# Stuff.net
KiCad netlist of a schematic drawn in Altium Designer
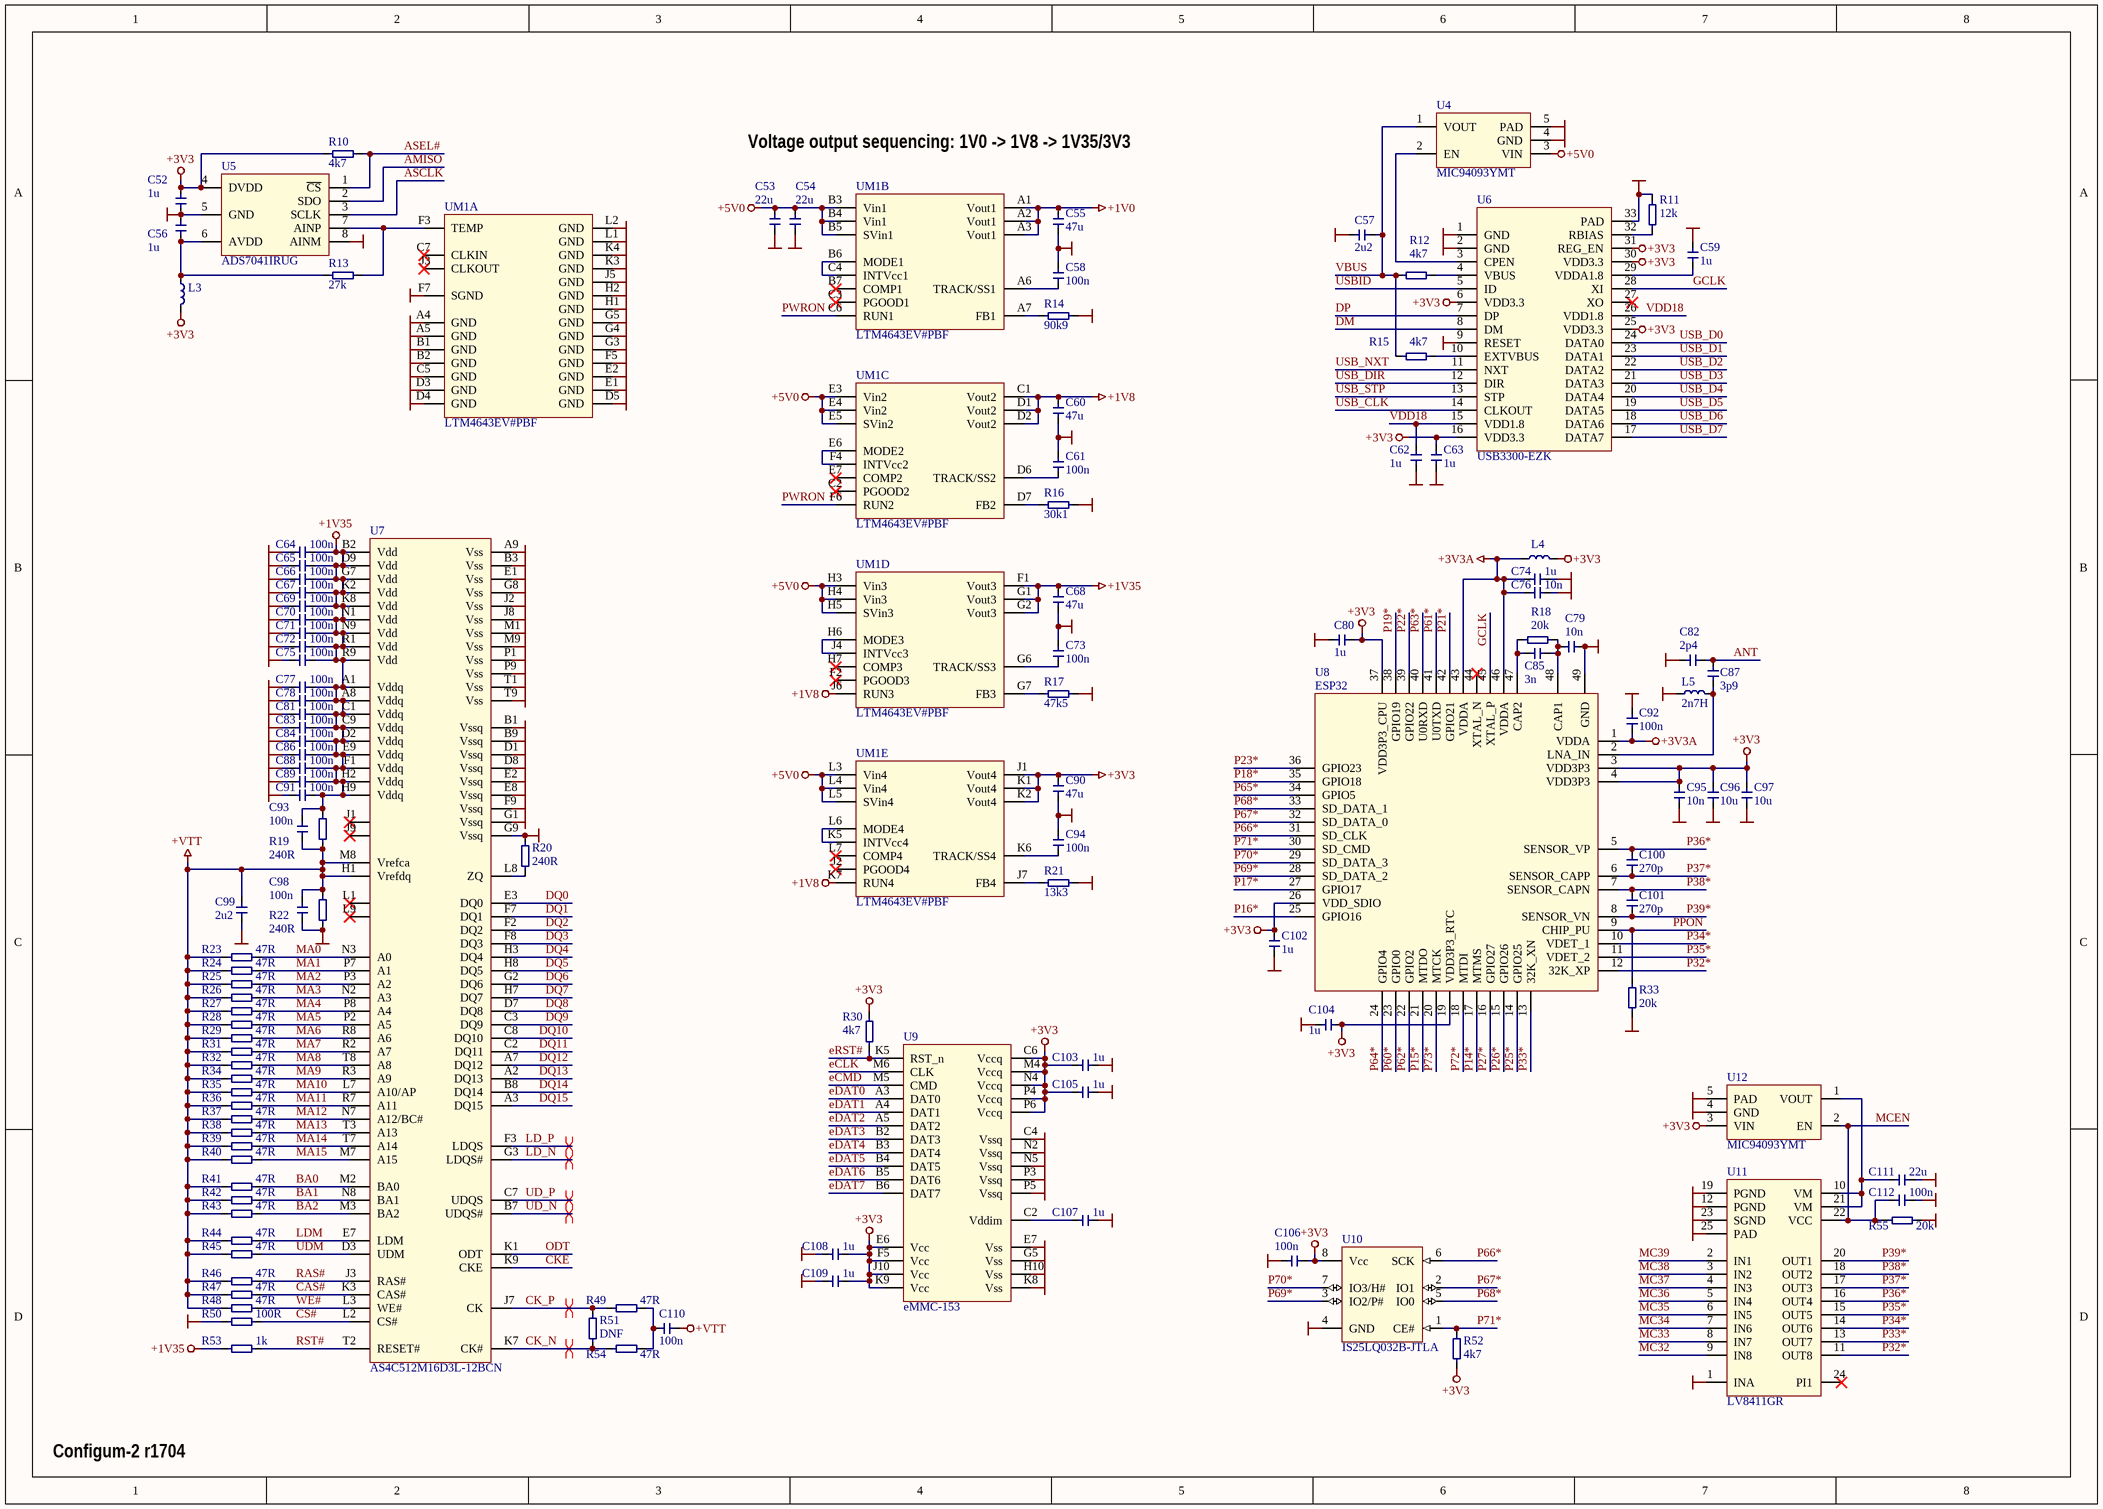
[diagram p0: Stuff.SchDoc]

(export (version "E")
  (design (tool "Eeschema 10.0.6"))
  (components
    (comp (ref "C52")
      (value "1u")
      (footprint "_0201")
      (description "Capacitor")
      (libsource (lib "Discretes") (part "Capacitor"))
    )
    (comp (ref "C53")
      (value "22u")
      (footprint "_0805_CAP")
      (description "Capacitor")
      (libsource (lib "Discretes") (part "Capacitor"))
    )
    (comp (ref "C54")
      (value "22u")
      (footprint "_0805_CAP")
      (description "Capacitor")
      (libsource (lib "Discretes") (part "Capacitor"))
    )
    (comp (ref "C55")
      (value "47u")
      (footprint "_0805_CAP")
      (description "Capacitor")
      (libsource (lib "Discretes") (part "Capacitor"))
    )
    (comp (ref "C56")
      (value "1u")
      (footprint "_0201")
      (description "Capacitor")
      (libsource (lib "Discretes") (part "Capacitor"))
    )
    (comp (ref "C57")
      (value "2u2")
      (footprint "_0201")
      (description "Capacitor")
      (libsource (lib "Discretes") (part "Capacitor"))
    )
    (comp (ref "C58")
      (value "100n")
      (footprint "_0201")
      (description "Capacitor")
      (libsource (lib "Discretes") (part "Capacitor"))
    )
    (comp (ref "C59")
      (value "1u")
      (footprint "_0201")
      (description "Capacitor")
      (libsource (lib "Discretes") (part "Capacitor"))
    )
    (comp (ref "C60")
      (value "47u")
      (footprint "_0805_CAP")
      (description "Capacitor")
      (libsource (lib "Discretes") (part "Capacitor"))
    )
    (comp (ref "C61")
      (value "100n")
      (footprint "_0201")
      (description "Capacitor")
      (libsource (lib "Discretes") (part "Capacitor"))
    )
    (comp (ref "C62")
      (value "1u")
      (footprint "_0201")
      (description "Capacitor")
      (libsource (lib "Discretes") (part "Capacitor"))
    )
    (comp (ref "C63")
      (value "1u")
      (footprint "_0201")
      (description "Capacitor")
      (libsource (lib "Discretes") (part "Capacitor"))
    )
    (comp (ref "C64")
      (value "100n")
      (footprint "_0201")
      (description "Capacitor")
      (libsource (lib "Discretes") (part "Capacitor"))
    )
    (comp (ref "C65")
      (value "100n")
      (footprint "_0201")
      (description "Capacitor")
      (libsource (lib "Discretes") (part "Capacitor"))
    )
    (comp (ref "C66")
      (value "100n")
      (footprint "_0201")
      (description "Capacitor")
      (libsource (lib "Discretes") (part "Capacitor"))
    )
    (comp (ref "C67")
      (value "100n")
      (footprint "_0201")
      (description "Capacitor")
      (libsource (lib "Discretes") (part "Capacitor"))
    )
    (comp (ref "C68")
      (value "47u")
      (footprint "_0805_CAP")
      (description "Capacitor")
      (libsource (lib "Discretes") (part "Capacitor"))
    )
    (comp (ref "C69")
      (value "100n")
      (footprint "_0201")
      (description "Capacitor")
      (libsource (lib "Discretes") (part "Capacitor"))
    )
    (comp (ref "C70")
      (value "100n")
      (footprint "_0201")
      (description "Capacitor")
      (libsource (lib "Discretes") (part "Capacitor"))
    )
    (comp (ref "C71")
      (value "100n")
      (footprint "_0201")
      (description "Capacitor")
      (libsource (lib "Discretes") (part "Capacitor"))
    )
    (comp (ref "C72")
      (value "100n")
      (footprint "_0201")
      (description "Capacitor")
      (libsource (lib "Discretes") (part "Capacitor"))
    )
    (comp (ref "C73")
      (value "100n")
      (footprint "_0201")
      (description "Capacitor")
      (libsource (lib "Discretes") (part "Capacitor"))
    )
    (comp (ref "C74")
      (value "1u")
      (footprint "_0201")
      (description "Capacitor")
      (libsource (lib "Discretes") (part "Capacitor"))
    )
    (comp (ref "C75")
      (value "100n")
      (footprint "_0201")
      (description "Capacitor")
      (libsource (lib "Discretes") (part "Capacitor"))
    )
    (comp (ref "C76")
      (value "10n")
      (footprint "_0201")
      (description "Capacitor")
      (libsource (lib "Discretes") (part "Capacitor"))
    )
    (comp (ref "C77")
      (value "100n")
      (footprint "_0201")
      (description "Capacitor")
      (libsource (lib "Discretes") (part "Capacitor"))
    )
    (comp (ref "C78")
      (value "100n")
      (footprint "_0201")
      (description "Capacitor")
      (libsource (lib "Discretes") (part "Capacitor"))
    )
    (comp (ref "C79")
      (value "10n")
      (footprint "_0201")
      (description "Capacitor")
      (libsource (lib "Discretes") (part "Capacitor"))
    )
    (comp (ref "C80")
      (value "1u")
      (footprint "_0201")
      (description "Capacitor")
      (libsource (lib "Discretes") (part "Capacitor"))
    )
    (comp (ref "C81")
      (value "100n")
      (footprint "_0201")
      (description "Capacitor")
      (libsource (lib "Discretes") (part "Capacitor"))
    )
    (comp (ref "C82")
      (value "2p4")
      (footprint "_0201")
      (description "Capacitor")
      (libsource (lib "Discretes") (part "Capacitor"))
    )
    (comp (ref "C83")
      (value "100n")
      (footprint "_0201")
      (description "Capacitor")
      (libsource (lib "Discretes") (part "Capacitor"))
    )
    (comp (ref "C84")
      (value "100n")
      (footprint "_0201")
      (description "Capacitor")
      (libsource (lib "Discretes") (part "Capacitor"))
    )
    (comp (ref "C85")
      (value "3n")
      (footprint "_0201")
      (description "Capacitor")
      (libsource (lib "Discretes") (part "Capacitor"))
    )
    (comp (ref "C86")
      (value "100n")
      (footprint "_0201")
      (description "Capacitor")
      (libsource (lib "Discretes") (part "Capacitor"))
    )
    (comp (ref "C87")
      (value "3p9")
      (footprint "_0201")
      (description "Capacitor")
      (libsource (lib "Discretes") (part "Capacitor"))
    )
    (comp (ref "C88")
      (value "100n")
      (footprint "_0201")
      (description "Capacitor")
      (libsource (lib "Discretes") (part "Capacitor"))
    )
    (comp (ref "C89")
      (value "100n")
      (footprint "_0201")
      (description "Capacitor")
      (libsource (lib "Discretes") (part "Capacitor"))
    )
    (comp (ref "C90")
      (value "47u")
      (footprint "_0805_CAP")
      (description "Capacitor")
      (libsource (lib "Discretes") (part "Capacitor"))
    )
    (comp (ref "C91")
      (value "100n")
      (footprint "_0201")
      (description "Capacitor")
      (libsource (lib "Discretes") (part "Capacitor"))
    )
    (comp (ref "C92")
      (value "100n")
      (footprint "_0201")
      (description "Capacitor")
      (libsource (lib "Discretes") (part "Capacitor"))
    )
    (comp (ref "C93")
      (value "100n")
      (footprint "_0201")
      (description "Capacitor")
      (libsource (lib "Discretes") (part "Capacitor"))
    )
    (comp (ref "C94")
      (value "100n")
      (footprint "_0201")
      (description "Capacitor")
      (libsource (lib "Discretes") (part "Capacitor"))
    )
    (comp (ref "C95")
      (value "10n")
      (footprint "_0201")
      (description "Capacitor")
      (libsource (lib "Discretes") (part "Capacitor"))
    )
    (comp (ref "C96")
      (value "10u")
      (footprint "_0603")
      (description "Capacitor")
      (libsource (lib "Discretes") (part "Capacitor"))
    )
    (comp (ref "C97")
      (value "10u")
      (footprint "_0603")
      (description "Capacitor")
      (libsource (lib "Discretes") (part "Capacitor"))
    )
    (comp (ref "C98")
      (value "100n")
      (footprint "_0201")
      (description "Capacitor")
      (libsource (lib "Discretes") (part "Capacitor"))
    )
    (comp (ref "C99")
      (value "2u2")
      (footprint "_0201")
      (description "Capacitor")
      (libsource (lib "Discretes") (part "Capacitor"))
    )
    (comp (ref "C100")
      (value "270p")
      (footprint "_0201")
      (description "Capacitor")
      (libsource (lib "Discretes") (part "Capacitor"))
    )
    (comp (ref "C101")
      (value "270p")
      (footprint "_0201")
      (description "Capacitor")
      (libsource (lib "Discretes") (part "Capacitor"))
    )
    (comp (ref "C102")
      (value "1u")
      (footprint "_0201")
      (description "Capacitor")
      (libsource (lib "Discretes") (part "Capacitor"))
    )
    (comp (ref "C103")
      (value "1u")
      (footprint "_0201")
      (description "Capacitor")
      (libsource (lib "Discretes") (part "Capacitor"))
    )
    (comp (ref "C104")
      (value "1u")
      (footprint "_0201")
      (description "Capacitor")
      (libsource (lib "Discretes") (part "Capacitor"))
    )
    (comp (ref "C105")
      (value "1u")
      (footprint "_0201")
      (description "Capacitor")
      (libsource (lib "Discretes") (part "Capacitor"))
    )
    (comp (ref "C106")
      (value "100n")
      (footprint "_0201")
      (description "Capacitor")
      (libsource (lib "Discretes") (part "Capacitor"))
    )
    (comp (ref "C107")
      (value "1u")
      (footprint "_0201")
      (description "Capacitor")
      (libsource (lib "Discretes") (part "Capacitor"))
    )
    (comp (ref "C108")
      (value "1u")
      (footprint "_0201")
      (description "Capacitor")
      (libsource (lib "Discretes") (part "Capacitor"))
    )
    (comp (ref "C109")
      (value "1u")
      (footprint "_0201")
      (description "Capacitor")
      (libsource (lib "Discretes") (part "Capacitor"))
    )
    (comp (ref "C110")
      (value "100n")
      (footprint "_0201")
      (description "Capacitor")
      (libsource (lib "Discretes") (part "Capacitor"))
    )
    (comp (ref "C111")
      (value "22u")
      (footprint "_0805_CAP")
      (description "Capacitor")
      (libsource (lib "Discretes") (part "Capacitor"))
    )
    (comp (ref "C112")
      (value "100n")
      (footprint "_0201")
      (description "Capacitor")
      (libsource (lib "Discretes") (part "Capacitor"))
    )
    (comp (ref "L3")
      (value "60R/100MHz")
      (footprint "_0201")
      (description "Inductor")
      (libsource (lib "Discretes") (part "Inductor"))
    )
    (comp (ref "L4")
      (value "60R/100MHz")
      (footprint "_0201")
      (description "Inductor")
      (libsource (lib "") (part "Inductor_1"))
    )
    (comp (ref "L5")
      (value "2n7H")
      (footprint "_0201")
      (description "Inductor")
      (libsource (lib "") (part "Inductor_1"))
    )
    (comp (ref "R10")
      (value "4k7")
      (footprint "_0201")
      (description "Resistor")
      (libsource (lib "") (part "Resistor_2"))
    )
    (comp (ref "R11")
      (value "12k")
      (footprint "_0201")
      (description "Resistor")
      (libsource (lib "") (part "Resistor_3"))
    )
    (comp (ref "R12")
      (value "4k7")
      (footprint "_0201")
      (description "Resistor")
      (libsource (lib "Discretes") (part "Resistor"))
    )
    (comp (ref "R13")
      (value "27k")
      (footprint "_0201")
      (description "Resistor")
      (libsource (lib "") (part "Resistor_2"))
    )
    (comp (ref "R14")
      (value "90k9")
      (footprint "_0201")
      (description "Resistor")
      (libsource (lib "Discretes") (part "Resistor"))
    )
    (comp (ref "R15")
      (value "4k7")
      (footprint "_0201")
      (description "Resistor")
      (libsource (lib "Discretes") (part "Resistor"))
    )
    (comp (ref "R16")
      (value "30k1")
      (footprint "_0201")
      (description "Resistor")
      (libsource (lib "Discretes") (part "Resistor"))
    )
    (comp (ref "R17")
      (value "47k5")
      (footprint "_0201")
      (description "Resistor")
      (libsource (lib "Discretes") (part "Resistor"))
    )
    (comp (ref "R18")
      (value "20k")
      (footprint "_0201")
      (description "Resistor")
      (libsource (lib "Discretes") (part "Resistor"))
    )
    (comp (ref "R19")
      (value "240R")
      (footprint "_0201")
      (description "Resistor")
      (libsource (lib "") (part "Resistor_1"))
    )
    (comp (ref "R20")
      (value "240R")
      (footprint "_0201")
      (description "Resistor")
      (libsource (lib "") (part "Resistor_1"))
    )
    (comp (ref "R21")
      (value "13k3")
      (footprint "_0201")
      (description "Resistor")
      (libsource (lib "Discretes") (part "Resistor"))
    )
    (comp (ref "R22")
      (value "240R")
      (footprint "_0201")
      (description "Resistor")
      (libsource (lib "") (part "Resistor_1"))
    )
    (comp (ref "R23")
      (value "47R")
      (footprint "_0201")
      (description "Resistor")
      (libsource (lib "") (part "Resistor_1"))
    )
    (comp (ref "R24")
      (value "47R")
      (footprint "_0201")
      (description "Resistor")
      (libsource (lib "") (part "Resistor_1"))
    )
    (comp (ref "R25")
      (value "47R")
      (footprint "_0201")
      (description "Resistor")
      (libsource (lib "") (part "Resistor_1"))
    )
    (comp (ref "R26")
      (value "47R")
      (footprint "_0201")
      (description "Resistor")
      (libsource (lib "") (part "Resistor_1"))
    )
    (comp (ref "R27")
      (value "47R")
      (footprint "_0201")
      (description "Resistor")
      (libsource (lib "") (part "Resistor_1"))
    )
    (comp (ref "R28")
      (value "47R")
      (footprint "_0201")
      (description "Resistor")
      (libsource (lib "") (part "Resistor_1"))
    )
    (comp (ref "R29")
      (value "47R")
      (footprint "_0201")
      (description "Resistor")
      (libsource (lib "") (part "Resistor_1"))
    )
    (comp (ref "R30")
      (value "4k7")
      (footprint "_0201")
      (description "Resistor")
      (libsource (lib "") (part "Resistor_1"))
    )
    (comp (ref "R31")
      (value "47R")
      (footprint "_0201")
      (description "Resistor")
      (libsource (lib "") (part "Resistor_1"))
    )
    (comp (ref "R32")
      (value "47R")
      (footprint "_0201")
      (description "Resistor")
      (libsource (lib "") (part "Resistor_1"))
    )
    (comp (ref "R33")
      (value "20k")
      (footprint "_0201")
      (description "Resistor")
      (libsource (lib "") (part "Resistor_1"))
    )
    (comp (ref "R34")
      (value "47R")
      (footprint "_0201")
      (description "Resistor")
      (libsource (lib "") (part "Resistor_1"))
    )
    (comp (ref "R35")
      (value "47R")
      (footprint "_0201")
      (description "Resistor")
      (libsource (lib "") (part "Resistor_1"))
    )
    (comp (ref "R36")
      (value "47R")
      (footprint "_0201")
      (description "Resistor")
      (libsource (lib "") (part "Resistor_1"))
    )
    (comp (ref "R37")
      (value "47R")
      (footprint "_0201")
      (description "Resistor")
      (libsource (lib "") (part "Resistor_1"))
    )
    (comp (ref "R38")
      (value "47R")
      (footprint "_0201")
      (description "Resistor")
      (libsource (lib "") (part "Resistor_1"))
    )
    (comp (ref "R39")
      (value "47R")
      (footprint "_0201")
      (description "Resistor")
      (libsource (lib "") (part "Resistor_1"))
    )
    (comp (ref "R40")
      (value "47R")
      (footprint "_0201")
      (description "Resistor")
      (libsource (lib "") (part "Resistor_1"))
    )
    (comp (ref "R41")
      (value "47R")
      (footprint "_0201")
      (description "Resistor")
      (libsource (lib "") (part "Resistor_1"))
    )
    (comp (ref "R42")
      (value "47R")
      (footprint "_0201")
      (description "Resistor")
      (libsource (lib "") (part "Resistor_1"))
    )
    (comp (ref "R43")
      (value "47R")
      (footprint "_0201")
      (description "Resistor")
      (libsource (lib "") (part "Resistor_1"))
    )
    (comp (ref "R44")
      (value "47R")
      (footprint "_0201")
      (description "Resistor")
      (libsource (lib "") (part "Resistor_1"))
    )
    (comp (ref "R45")
      (value "47R")
      (footprint "_0201")
      (description "Resistor")
      (libsource (lib "") (part "Resistor_1"))
    )
    (comp (ref "R46")
      (value "47R")
      (footprint "_0201")
      (description "Resistor")
      (libsource (lib "") (part "Resistor_1"))
    )
    (comp (ref "R47")
      (value "47R")
      (footprint "_0201")
      (description "Resistor")
      (libsource (lib "") (part "Resistor_1"))
    )
    (comp (ref "R48")
      (value "47R")
      (footprint "_0201")
      (description "Resistor")
      (libsource (lib "") (part "Resistor_1"))
    )
    (comp (ref "R49")
      (value "47R")
      (footprint "_0201")
      (description "Resistor")
      (libsource (lib "") (part "Resistor_2"))
    )
    (comp (ref "R50")
      (value "100R")
      (footprint "_0201")
      (description "Resistor")
      (libsource (lib "") (part "Resistor_1"))
    )
    (comp (ref "R51")
      (value "DNF")
      (footprint "_0201")
      (description "Resistor")
      (libsource (lib "") (part "Resistor_3"))
    )
    (comp (ref "R52")
      (value "4k7")
      (footprint "_0201")
      (description "Resistor")
      (libsource (lib "Discretes") (part "Resistor"))
    )
    (comp (ref "R53")
      (value "1k")
      (footprint "_0201")
      (description "Resistor")
      (libsource (lib "") (part "Resistor_1"))
    )
    (comp (ref "R54")
      (value "47R")
      (footprint "_0201")
      (description "Resistor")
      (libsource (lib "") (part "Resistor_2"))
    )
    (comp (ref "R55")
      (value "20k")
      (footprint "_0201")
      (description "Resistor")
      (libsource (lib "") (part "Resistor_2"))
    )
    (comp (ref "U4")
      (value "MIC94093YMT")
      (footprint "DFN65P120x120-4")
      (description "High-side load switch for consumer applications")
      (fields (field (name "MANUFACTURER") "Microchip"))
      (libsource (lib "") (part "MIC9409x (1.2x1.2 Thin MLF)_1"))
    )
    (comp (ref "U5")
      (value "ADS7041IRUG")
      (footprint "X2QFN50P150X150-8")
      (description "Ultra-Low Power, Ultra-Small Size, 10-Bit, 1-MSPS, SAR ADC")
      (fields (field (name "MANUFACTURER") "Texas Instruments"))
      (libsource (lib "IC Interface") (part "ADS7041 (Q2QFN 1.5x1.5)"))
    )
    (comp (ref "U6")
      (value "USB3300-EZK")
      (footprint "QFN50P500X500-32V5N")
      (description "Hi-Speed USB Host, Device or OTG PHY with  ULPI Low Pin Interface")
      (fields (field (name "MANUFACTURER") "Microchip"))
      (libsource (lib "IC Interface") (part "USB3300"))
    )
    (comp (ref "U7")
      (value "AS4C512M16D3L-12BCN")
      (footprint "BGA96C80P9X16_900X1400X120")
      (description "DDR3L RAM 8Gb (512Mx16)")
      (fields (field (name "MANUFACTURER") "Alliance Semiconductor"))
      (libsource (lib "IC Other Functions") (part "AS4C512M16D3L"))
    )
    (comp (ref "U8")
      (value "ESP32")
      (footprint "QFN40P600X600X90-49N-S470")
      (description "WiFi, BT4.2, 2xCPU integrated solution")
      (fields (field (name "MANUFACTURER") "Espressif"))
      (libsource (lib "IC RF Digital") (part "ESP32"))
    )
    (comp (ref "U9")
      (value "eMMC-153")
      (footprint "BGA153C50P14X14_1150X1300X90")
      (description "eMMC memory")
      (fields (field (name "MANUFACTURER") "Micron"))
      (libsource (lib "IC Other Functions") (part "eMMC"))
    )
    (comp (ref "U10")
      (value "IS25LQ032B-JTLA")
      (footprint "SON80P300X60_HS-9L")
      (description "Standard 8-pin SPI flash memory")
      (libsource (lib "IC Other Functions") (part "SPI Flash 8pin"))
    )
    (comp (ref "U11")
      (value "LV8411GR")
      (footprint "QFN40P300X300X80_HS-25L")
      (description "4-channel single chip motor driver IC")
      (fields (field (name "MANUFACTURER") "On Semiconductor"))
      (libsource (lib "IC Drivers and Switches") (part "LV8411GR"))
    )
    (comp (ref "U12")
      (value "MIC94093YMT")
      (footprint "DFN65P120x120-4")
      (description "High-side load switch for consumer applications")
      (fields (field (name "MANUFACTURER") "Microchip"))
      (libsource (lib "IC Drivers and Switches") (part "MIC9409x (1.2x1.2 Thin MLF)"))
    )
    (comp (ref "UM1")
      (value "LTM4643EV#PBF")
      (footprint "LGA77C127P7X11_900X1500X182")
      (description "Ultrathin Quad Module Regulator with Configurable 3A Output Array")
      (fields (field (name "MANUFACTURER") "Linear"))
      (libsource (lib "") (part "LTM4643_1"))
    )
  )
  (nets
    (net (code "1") (name "+1V0") (class "Default")
      (node (ref "C55") (pin "1") (pintype "passive"))
      (node (ref "UM1") (pin "A1") (pinfunction "Vout1_A1") (pintype "passive"))
      (node (ref "UM1") (pin "A2") (pinfunction "Vout1_A2") (pintype "passive"))
      (node (ref "UM1") (pin "A3") (pinfunction "Vout1_A3") (pintype "passive"))
    )
    (net (code "2") (name "+1V8") (class "Default")
      (node (ref "C60") (pin "1") (pintype "passive"))
      (node (ref "UM1") (pin "C1") (pinfunction "Vout2_C1") (pintype "passive"))
      (node (ref "UM1") (pin "D1") (pinfunction "Vout2_D1") (pintype "passive"))
      (node (ref "UM1") (pin "D2") (pinfunction "Vout2_D2") (pintype "passive"))
      (node (ref "UM1") (pin "J6") (pinfunction "RUN3_J6") (pintype "passive"))
      (node (ref "UM1") (pin "K7") (pinfunction "RUN4_K7") (pintype "passive"))
    )
    (net (code "3") (name "+1V35") (class "Default")
      (node (ref "C64") (pin "1") (pintype "passive"))
      (node (ref "C65") (pin "1") (pintype "passive"))
      (node (ref "C66") (pin "1") (pintype "passive"))
      (node (ref "C67") (pin "1") (pintype "passive"))
      (node (ref "C68") (pin "1") (pintype "passive"))
      (node (ref "C69") (pin "1") (pintype "passive"))
      (node (ref "C70") (pin "1") (pintype "passive"))
      (node (ref "C71") (pin "1") (pintype "passive"))
      (node (ref "C72") (pin "1") (pintype "passive"))
      (node (ref "C75") (pin "1") (pintype "passive"))
      (node (ref "C77") (pin "1") (pintype "passive"))
      (node (ref "C78") (pin "1") (pintype "passive"))
      (node (ref "C81") (pin "1") (pintype "passive"))
      (node (ref "C83") (pin "1") (pintype "passive"))
      (node (ref "C84") (pin "1") (pintype "passive"))
      (node (ref "C86") (pin "1") (pintype "passive"))
      (node (ref "C88") (pin "1") (pintype "passive"))
      (node (ref "C89") (pin "1") (pintype "passive"))
      (node (ref "C91") (pin "1") (pintype "passive"))
      (node (ref "C93") (pin "1") (pintype "passive"))
      (node (ref "R19") (pin "2") (pintype "passive"))
      (node (ref "R53") (pin "1") (pintype "passive"))
      (node (ref "U7") (pin "A1") (pinfunction "Vddq_A1") (pintype "passive"))
      (node (ref "U7") (pin "A8") (pinfunction "Vddq_A8") (pintype "passive"))
      (node (ref "U7") (pin "B2") (pinfunction "Vdd_B2") (pintype "passive"))
      (node (ref "U7") (pin "C1") (pinfunction "Vddq_C1") (pintype "passive"))
      (node (ref "U7") (pin "C9") (pinfunction "Vddq_C9") (pintype "passive"))
      (node (ref "U7") (pin "D2") (pinfunction "Vddq_D2") (pintype "passive"))
      (node (ref "U7") (pin "D9") (pinfunction "Vdd_D9") (pintype "passive"))
      (node (ref "U7") (pin "E9") (pinfunction "Vddq_E9") (pintype "passive"))
      (node (ref "U7") (pin "F1") (pinfunction "Vddq_F1") (pintype "passive"))
      (node (ref "U7") (pin "G7") (pinfunction "Vdd_G7") (pintype "passive"))
      (node (ref "U7") (pin "H2") (pinfunction "Vddq_H2") (pintype "passive"))
      (node (ref "U7") (pin "H9") (pinfunction "Vddq_H9") (pintype "passive"))
      (node (ref "U7") (pin "K2") (pinfunction "Vdd_K2") (pintype "passive"))
      (node (ref "U7") (pin "K8") (pinfunction "Vdd_K8") (pintype "passive"))
      (node (ref "U7") (pin "N1") (pinfunction "Vdd_N1") (pintype "passive"))
      (node (ref "U7") (pin "N9") (pinfunction "Vdd_N9") (pintype "passive"))
      (node (ref "U7") (pin "R1") (pinfunction "Vdd_R1") (pintype "passive"))
      (node (ref "U7") (pin "R9") (pinfunction "Vdd_R9") (pintype "passive"))
      (node (ref "UM1") (pin "F1") (pinfunction "Vout3_F1") (pintype "passive"))
      (node (ref "UM1") (pin "G1") (pinfunction "Vout3_G1") (pintype "passive"))
      (node (ref "UM1") (pin "G2") (pinfunction "Vout3_G2") (pintype "passive"))
    )
    (net (code "4") (name "+3V3") (class "Default")
      (node (ref "C102") (pin "1") (pintype "passive"))
      (node (ref "C103") (pin "2") (pintype "passive"))
      (node (ref "C104") (pin "1") (pintype "passive"))
      (node (ref "C105") (pin "2") (pintype "passive"))
      (node (ref "C106") (pin "1") (pintype "passive"))
      (node (ref "C108") (pin "1") (pintype "passive"))
      (node (ref "C109") (pin "2") (pintype "passive"))
      (node (ref "C52") (pin "2") (pintype "passive"))
      (node (ref "C63") (pin "2") (pintype "passive"))
      (node (ref "C80") (pin "2") (pintype "passive"))
      (node (ref "C90") (pin "1") (pintype "passive"))
      (node (ref "C95") (pin "2") (pintype "passive"))
      (node (ref "C96") (pin "2") (pintype "passive"))
      (node (ref "C97") (pin "2") (pintype "passive"))
      (node (ref "L3") (pin "1") (pintype "passive"))
      (node (ref "L4") (pin "2") (pintype "passive"))
      (node (ref "R10") (pin "2") (pintype "passive"))
      (node (ref "R30") (pin "2") (pintype "passive"))
      (node (ref "R52") (pin "1") (pintype "passive"))
      (node (ref "U10") (pin "8") (pinfunction "Vcc_8") (pintype "power_in"))
      (node (ref "U12") (pin "3") (pinfunction "VIN_3") (pintype "passive"))
      (node (ref "U5") (pin "4") (pinfunction "DVDD_4") (pintype "passive"))
      (node (ref "U6") (pin "16") (pinfunction "VDD3.3_16") (pintype "passive"))
      (node (ref "U6") (pin "25") (pinfunction "VDD3.3_25") (pintype "passive"))
      (node (ref "U6") (pin "30") (pinfunction "VDD3.3_30") (pintype "passive"))
      (node (ref "U6") (pin "31") (pinfunction "REG_EN_31") (pintype "passive"))
      (node (ref "U6") (pin "6") (pinfunction "VDD3.3_6") (pintype "passive"))
      (node (ref "U8") (pin "19") (pinfunction "VDD3P3_RTC_19") (pintype "passive"))
      (node (ref "U8") (pin "26") (pinfunction "VDD_SDIO_26") (pintype "passive"))
      (node (ref "U8") (pin "3") (pinfunction "VDD3P3_3") (pintype "passive"))
      (node (ref "U8") (pin "37") (pinfunction "VDD3P3_CPU_37") (pintype "passive"))
      (node (ref "U8") (pin "4") (pinfunction "VDD3P3_4") (pintype "passive"))
      (node (ref "U9") (pin "C6") (pinfunction "Vccq_C6") (pintype "passive"))
      (node (ref "U9") (pin "E6") (pinfunction "Vcc_E6") (pintype "passive"))
      (node (ref "U9") (pin "F5") (pinfunction "Vcc_F5") (pintype "passive"))
      (node (ref "U9") (pin "J10") (pinfunction "Vcc_J10") (pintype "passive"))
      (node (ref "U9") (pin "K9") (pinfunction "Vcc_K9") (pintype "passive"))
      (node (ref "U9") (pin "M4") (pinfunction "Vccq_M4") (pintype "passive"))
      (node (ref "U9") (pin "N4") (pinfunction "Vccq_N4") (pintype "passive"))
      (node (ref "U9") (pin "P4") (pinfunction "Vccq_P4") (pintype "passive"))
      (node (ref "U9") (pin "P6") (pinfunction "Vccq_P6") (pintype "passive"))
      (node (ref "UM1") (pin "J1") (pinfunction "Vout4_J1") (pintype "passive"))
      (node (ref "UM1") (pin "K1") (pinfunction "Vout4_K1") (pintype "passive"))
      (node (ref "UM1") (pin "K2") (pinfunction "Vout4_K2") (pintype "passive"))
    )
    (net (code "5") (name "+3V3A") (class "Default")
      (node (ref "C74") (pin "2") (pintype "passive"))
      (node (ref "C76") (pin "2") (pintype "passive"))
      (node (ref "C92") (pin "2") (pintype "passive"))
      (node (ref "L4") (pin "1") (pintype "passive"))
      (node (ref "U8") (pin "1") (pinfunction "VDDA_1") (pintype "passive"))
      (node (ref "U8") (pin "43") (pinfunction "VDDA_43") (pintype "passive"))
      (node (ref "U8") (pin "46") (pinfunction "VDDA_46") (pintype "passive"))
    )
    (net (code "6") (name "+5V0") (class "Default")
      (node (ref "C53") (pin "1") (pintype "passive"))
      (node (ref "C54") (pin "1") (pintype "passive"))
      (node (ref "U4") (pin "3") (pinfunction "VIN_3") (pintype "passive"))
      (node (ref "UM1") (pin "B3") (pinfunction "Vin1_B3") (pintype "passive"))
      (node (ref "UM1") (pin "B4") (pinfunction "Vin1_B4") (pintype "passive"))
      (node (ref "UM1") (pin "B5") (pinfunction "SVin1_B5") (pintype "passive"))
      (node (ref "UM1") (pin "E3") (pinfunction "Vin2_E3") (pintype "passive"))
      (node (ref "UM1") (pin "E4") (pinfunction "Vin2_E4") (pintype "passive"))
      (node (ref "UM1") (pin "E5") (pinfunction "SVin2_E5") (pintype "passive"))
      (node (ref "UM1") (pin "H3") (pinfunction "Vin3_H3") (pintype "passive"))
      (node (ref "UM1") (pin "H4") (pinfunction "Vin3_H4") (pintype "passive"))
      (node (ref "UM1") (pin "H5") (pinfunction "SVin3_H5") (pintype "passive"))
      (node (ref "UM1") (pin "L3") (pinfunction "Vin4_L3") (pintype "passive"))
      (node (ref "UM1") (pin "L4") (pinfunction "Vin4_L4") (pintype "passive"))
      (node (ref "UM1") (pin "L5") (pinfunction "SVin4_L5") (pintype "passive"))
    )
    (net (code "7") (name "+VTT") (class "Default")
      (node (ref "C110") (pin "2") (pintype "passive"))
      (node (ref "C93") (pin "2") (pintype "passive"))
      (node (ref "C98") (pin "1") (pintype "passive"))
      (node (ref "C99") (pin "1") (pintype "passive"))
      (node (ref "R19") (pin "1") (pintype "passive"))
      (node (ref "R22") (pin "2") (pintype "passive"))
      (node (ref "R23") (pin "1") (pintype "passive"))
      (node (ref "R24") (pin "1") (pintype "passive"))
      (node (ref "R25") (pin "1") (pintype "passive"))
      (node (ref "R26") (pin "1") (pintype "passive"))
      (node (ref "R27") (pin "1") (pintype "passive"))
      (node (ref "R28") (pin "1") (pintype "passive"))
      (node (ref "R29") (pin "1") (pintype "passive"))
      (node (ref "R31") (pin "1") (pintype "passive"))
      (node (ref "R32") (pin "1") (pintype "passive"))
      (node (ref "R34") (pin "1") (pintype "passive"))
      (node (ref "R35") (pin "1") (pintype "passive"))
      (node (ref "R36") (pin "1") (pintype "passive"))
      (node (ref "R37") (pin "1") (pintype "passive"))
      (node (ref "R38") (pin "1") (pintype "passive"))
      (node (ref "R39") (pin "1") (pintype "passive"))
      (node (ref "R40") (pin "1") (pintype "passive"))
      (node (ref "R41") (pin "1") (pintype "passive"))
      (node (ref "R42") (pin "1") (pintype "passive"))
      (node (ref "R43") (pin "1") (pintype "passive"))
      (node (ref "R44") (pin "1") (pintype "passive"))
      (node (ref "R45") (pin "1") (pintype "passive"))
      (node (ref "R46") (pin "1") (pintype "passive"))
      (node (ref "R47") (pin "1") (pintype "passive"))
      (node (ref "R48") (pin "1") (pintype "passive"))
      (node (ref "U7") (pin "H1") (pinfunction "Vrefdq_H1") (pintype "passive"))
      (node (ref "U7") (pin "M8") (pinfunction "Vrefca_M8") (pintype "passive"))
    )
    (net (code "8") (name "/AMISO") (class "Default")
      (node (ref "U5") (pin "2") (pinfunction "SDO_2") (pintype "passive"))
    )
    (net (code "9") (name "/ANT") (class "Default")
      (node (ref "C82") (pin "2") (pintype "passive"))
      (node (ref "C87") (pin "1") (pintype "passive"))
    )
    (net (code "10") (name "/ASCLK") (class "Default")
      (node (ref "U5") (pin "3") (pinfunction "SCLK_3") (pintype "passive"))
    )
    (net (code "11") (name "/ASEL#") (class "Default")
      (node (ref "R10") (pin "1") (pintype "passive"))
      (node (ref "U5") (pin "1") (pinfunction "~{CS}_1") (pintype "passive"))
    )
    (net (code "12") (name "/BA0") (class "Default")
      (node (ref "R41") (pin "2") (pintype "passive"))
      (node (ref "U7") (pin "M2") (pinfunction "BA0_M2") (pintype "passive"))
    )
    (net (code "13") (name "/BA1") (class "Default")
      (node (ref "R42") (pin "2") (pintype "passive"))
      (node (ref "U7") (pin "N8") (pinfunction "BA1_N8") (pintype "passive"))
    )
    (net (code "14") (name "/BA2") (class "Default")
      (node (ref "R43") (pin "2") (pintype "passive"))
      (node (ref "U7") (pin "M3") (pinfunction "BA2_M3") (pintype "passive"))
    )
    (net (code "15") (name "/CAS#") (class "Default")
      (node (ref "R47") (pin "2") (pintype "passive"))
      (node (ref "U7") (pin "K3") (pinfunction "CAS#_K3") (pintype "passive"))
    )
    (net (code "16") (name "/CKE") (class "Default")
      (node (ref "U7") (pin "K9") (pinfunction "CKE_K9") (pintype "passive"))
    )
    (net (code "17") (name "/CK_N") (class "Default")
      (node (ref "R51") (pin "2") (pintype "passive"))
      (node (ref "R54") (pin "2") (pintype "passive"))
      (node (ref "U7") (pin "K7") (pinfunction "CK#_K7") (pintype "passive"))
    )
    (net (code "18") (name "/CK_P") (class "Default")
      (node (ref "R49") (pin "2") (pintype "passive"))
      (node (ref "R51") (pin "1") (pintype "passive"))
      (node (ref "U7") (pin "J7") (pinfunction "CK_J7") (pintype "passive"))
    )
    (net (code "19") (name "/CS#") (class "Default")
      (node (ref "R50") (pin "2") (pintype "passive"))
      (node (ref "U7") (pin "L2") (pinfunction "CS#_L2") (pintype "passive"))
    )
    (net (code "20") (name "/DM") (class "Default")
      (node (ref "U6") (pin "8") (pinfunction "DM_8") (pintype "passive"))
    )
    (net (code "21") (name "/DP") (class "Default")
      (node (ref "U6") (pin "7") (pinfunction "DP_7") (pintype "passive"))
    )
    (net (code "22") (name "/DQ0") (class "Default")
      (node (ref "U7") (pin "E3") (pinfunction "DQ0_E3") (pintype "passive"))
    )
    (net (code "23") (name "/DQ1") (class "Default")
      (node (ref "U7") (pin "F7") (pinfunction "DQ1_F7") (pintype "passive"))
    )
    (net (code "24") (name "/DQ2") (class "Default")
      (node (ref "U7") (pin "F2") (pinfunction "DQ2_F2") (pintype "passive"))
    )
    (net (code "25") (name "/DQ3") (class "Default")
      (node (ref "U7") (pin "F8") (pinfunction "DQ3_F8") (pintype "passive"))
    )
    (net (code "26") (name "/DQ4") (class "Default")
      (node (ref "U7") (pin "H3") (pinfunction "DQ4_H3") (pintype "passive"))
    )
    (net (code "27") (name "/DQ5") (class "Default")
      (node (ref "U7") (pin "H8") (pinfunction "DQ5_H8") (pintype "passive"))
    )
    (net (code "28") (name "/DQ6") (class "Default")
      (node (ref "U7") (pin "G2") (pinfunction "DQ6_G2") (pintype "passive"))
    )
    (net (code "29") (name "/DQ7") (class "Default")
      (node (ref "U7") (pin "H7") (pinfunction "DQ7_H7") (pintype "passive"))
    )
    (net (code "30") (name "/DQ8") (class "Default")
      (node (ref "U7") (pin "D7") (pinfunction "DQ8_D7") (pintype "passive"))
    )
    (net (code "31") (name "/DQ9") (class "Default")
      (node (ref "U7") (pin "C3") (pinfunction "DQ9_C3") (pintype "passive"))
    )
    (net (code "32") (name "/DQ10") (class "Default")
      (node (ref "U7") (pin "C8") (pinfunction "DQ10_C8") (pintype "passive"))
    )
    (net (code "33") (name "/DQ11") (class "Default")
      (node (ref "U7") (pin "C2") (pinfunction "DQ11_C2") (pintype "passive"))
    )
    (net (code "34") (name "/DQ12") (class "Default")
      (node (ref "U7") (pin "A7") (pinfunction "DQ12_A7") (pintype "passive"))
    )
    (net (code "35") (name "/DQ13") (class "Default")
      (node (ref "U7") (pin "A2") (pinfunction "DQ13_A2") (pintype "passive"))
    )
    (net (code "36") (name "/DQ14") (class "Default")
      (node (ref "U7") (pin "B8") (pinfunction "DQ14_B8") (pintype "passive"))
    )
    (net (code "37") (name "/DQ15") (class "Default")
      (node (ref "U7") (pin "A3") (pinfunction "DQ15_A3") (pintype "passive"))
    )
    (net (code "38") (name "/GCLK") (class "Default")
      (node (ref "U6") (pin "28") (pinfunction "XI_28") (pintype "passive"))
      (node (ref "U8") (pin "45") (pinfunction "XTAL_P_45") (pintype "passive"))
    )
    (net (code "39") (name "/LDM") (class "Default")
      (node (ref "R44") (pin "2") (pintype "passive"))
      (node (ref "U7") (pin "E7") (pinfunction "LDM_E7") (pintype "passive"))
    )
    (net (code "40") (name "/LD_N") (class "Default")
      (node (ref "U7") (pin "G3") (pinfunction "LDQS#_G3") (pintype "passive"))
    )
    (net (code "41") (name "/LD_P") (class "Default")
      (node (ref "U7") (pin "F3") (pinfunction "LDQS_F3") (pintype "passive"))
    )
    (net (code "42") (name "/MA0") (class "Default")
      (node (ref "R23") (pin "2") (pintype "passive"))
      (node (ref "U7") (pin "N3") (pinfunction "A0_N3") (pintype "passive"))
    )
    (net (code "43") (name "/MA1") (class "Default")
      (node (ref "R24") (pin "2") (pintype "passive"))
      (node (ref "U7") (pin "P7") (pinfunction "A1_P7") (pintype "passive"))
    )
    (net (code "44") (name "/MA2") (class "Default")
      (node (ref "R25") (pin "2") (pintype "passive"))
      (node (ref "U7") (pin "P3") (pinfunction "A2_P3") (pintype "passive"))
    )
    (net (code "45") (name "/MA3") (class "Default")
      (node (ref "R26") (pin "2") (pintype "passive"))
      (node (ref "U7") (pin "N2") (pinfunction "A3_N2") (pintype "passive"))
    )
    (net (code "46") (name "/MA4") (class "Default")
      (node (ref "R27") (pin "2") (pintype "passive"))
      (node (ref "U7") (pin "P8") (pinfunction "A4_P8") (pintype "passive"))
    )
    (net (code "47") (name "/MA5") (class "Default")
      (node (ref "R28") (pin "2") (pintype "passive"))
      (node (ref "U7") (pin "P2") (pinfunction "A5_P2") (pintype "passive"))
    )
    (net (code "48") (name "/MA6") (class "Default")
      (node (ref "R29") (pin "2") (pintype "passive"))
      (node (ref "U7") (pin "R8") (pinfunction "A6_R8") (pintype "passive"))
    )
    (net (code "49") (name "/MA7") (class "Default")
      (node (ref "R31") (pin "2") (pintype "passive"))
      (node (ref "U7") (pin "R2") (pinfunction "A7_R2") (pintype "passive"))
    )
    (net (code "50") (name "/MA8") (class "Default")
      (node (ref "R32") (pin "2") (pintype "passive"))
      (node (ref "U7") (pin "T8") (pinfunction "A8_T8") (pintype "passive"))
    )
    (net (code "51") (name "/MA9") (class "Default")
      (node (ref "R34") (pin "2") (pintype "passive"))
      (node (ref "U7") (pin "R3") (pinfunction "A9_R3") (pintype "passive"))
    )
    (net (code "52") (name "/MA10") (class "Default")
      (node (ref "R35") (pin "2") (pintype "passive"))
      (node (ref "U7") (pin "L7") (pinfunction "A10/AP_L7") (pintype "passive"))
    )
    (net (code "53") (name "/MA11") (class "Default")
      (node (ref "R36") (pin "2") (pintype "passive"))
      (node (ref "U7") (pin "R7") (pinfunction "A11_R7") (pintype "passive"))
    )
    (net (code "54") (name "/MA12") (class "Default")
      (node (ref "R37") (pin "2") (pintype "passive"))
      (node (ref "U7") (pin "N7") (pinfunction "A12/BC#_N7") (pintype "passive"))
    )
    (net (code "55") (name "/MA13") (class "Default")
      (node (ref "R38") (pin "2") (pintype "passive"))
      (node (ref "U7") (pin "T3") (pinfunction "A13_T3") (pintype "passive"))
    )
    (net (code "56") (name "/MA14") (class "Default")
      (node (ref "R39") (pin "2") (pintype "passive"))
      (node (ref "U7") (pin "T7") (pinfunction "A14_T7") (pintype "passive"))
    )
    (net (code "57") (name "/MA15") (class "Default")
      (node (ref "R40") (pin "2") (pintype "passive"))
      (node (ref "U7") (pin "M7") (pinfunction "A15_M7") (pintype "passive"))
    )
    (net (code "58") (name "/MC32") (class "Default")
      (node (ref "U11") (pin "9") (pinfunction "IN8_9") (pintype "passive"))
    )
    (net (code "59") (name "/MC33") (class "Default")
      (node (ref "U11") (pin "8") (pinfunction "IN7_8") (pintype "passive"))
    )
    (net (code "60") (name "/MC34") (class "Default")
      (node (ref "U11") (pin "7") (pinfunction "IN6_7") (pintype "passive"))
    )
    (net (code "61") (name "/MC35") (class "Default")
      (node (ref "U11") (pin "6") (pinfunction "IN5_6") (pintype "passive"))
    )
    (net (code "62") (name "/MC36") (class "Default")
      (node (ref "U11") (pin "5") (pinfunction "IN4_5") (pintype "passive"))
    )
    (net (code "63") (name "/MC37") (class "Default")
      (node (ref "U11") (pin "4") (pinfunction "IN3_4") (pintype "passive"))
    )
    (net (code "64") (name "/MC38") (class "Default")
      (node (ref "U11") (pin "3") (pinfunction "IN2_3") (pintype "passive"))
    )
    (net (code "65") (name "/MC39") (class "Default")
      (node (ref "U11") (pin "2") (pinfunction "IN1_2") (pintype "passive"))
    )
    (net (code "66") (name "/MCEN") (class "Default")
      (node (ref "C112") (pin "2") (pintype "passive"))
      (node (ref "R55") (pin "2") (pintype "passive"))
      (node (ref "U11") (pin "22") (pinfunction "VCC_22") (pintype "passive"))
      (node (ref "U12") (pin "2") (pinfunction "EN_2") (pintype "passive"))
    )
    (net (code "67") (name "/ODT") (class "Default")
      (node (ref "U7") (pin "K1") (pinfunction "ODT_K1") (pintype "passive"))
    )
    (net (code "68") (name "/P14*") (class "Default")
      (node (ref "U8") (pin "17") (pinfunction "MTMS_17") (pintype "passive"))
    )
    (net (code "69") (name "/P15*") (class "Default")
      (node (ref "U8") (pin "21") (pinfunction "MTDO_21") (pintype "passive"))
    )
    (net (code "70") (name "/P16*") (class "Default")
      (node (ref "U8") (pin "25") (pinfunction "GPIO16_25") (pintype "passive"))
    )
    (net (code "71") (name "/P17*") (class "Default")
      (node (ref "U8") (pin "27") (pinfunction "GPIO17_27") (pintype "passive"))
    )
    (net (code "72") (name "/P18*") (class "Default")
      (node (ref "U8") (pin "35") (pinfunction "GPIO18_35") (pintype "passive"))
    )
    (net (code "73") (name "/P19*") (class "Default")
      (node (ref "U8") (pin "38") (pinfunction "GPIO19_38") (pintype "passive"))
    )
    (net (code "74") (name "/P21*") (class "Default")
      (node (ref "U8") (pin "42") (pinfunction "GPIO21_42") (pintype "passive"))
    )
    (net (code "75") (name "/P22*") (class "Default")
      (node (ref "U8") (pin "39") (pinfunction "GPIO22_39") (pintype "passive"))
    )
    (net (code "76") (name "/P23*") (class "Default")
      (node (ref "U8") (pin "36") (pinfunction "GPIO23_36") (pintype "passive"))
    )
    (net (code "77") (name "/P25*") (class "Default")
      (node (ref "U8") (pin "14") (pinfunction "GPIO25_14") (pintype "passive"))
    )
    (net (code "78") (name "/P26*") (class "Default")
      (node (ref "U8") (pin "15") (pinfunction "GPIO26_15") (pintype "passive"))
    )
    (net (code "79") (name "/P27*") (class "Default")
      (node (ref "U8") (pin "16") (pinfunction "GPIO27_16") (pintype "passive"))
    )
    (net (code "80") (name "/P32*") (class "Default")
      (node (ref "U11") (pin "11") (pinfunction "OUT8_11") (pintype "passive"))
      (node (ref "U8") (pin "12") (pinfunction "32K_XP_12") (pintype "passive"))
    )
    (net (code "81") (name "/P33*") (class "Default")
      (node (ref "U11") (pin "13") (pinfunction "OUT7_13") (pintype "passive"))
      (node (ref "U8") (pin "13") (pinfunction "32K_XN_13") (pintype "passive"))
    )
    (net (code "82") (name "/P34*") (class "Default")
      (node (ref "U11") (pin "14") (pinfunction "OUT6_14") (pintype "passive"))
      (node (ref "U8") (pin "10") (pinfunction "VDET_1_10") (pintype "passive"))
    )
    (net (code "83") (name "/P35*") (class "Default")
      (node (ref "U11") (pin "15") (pinfunction "OUT5_15") (pintype "passive"))
      (node (ref "U8") (pin "11") (pinfunction "VDET_2_11") (pintype "passive"))
    )
    (net (code "84") (name "/P36*") (class "Default")
      (node (ref "C100") (pin "2") (pintype "passive"))
      (node (ref "U11") (pin "16") (pinfunction "OUT4_16") (pintype "passive"))
      (node (ref "U8") (pin "5") (pinfunction "SENSOR_VP_5") (pintype "passive"))
    )
    (net (code "85") (name "/P37*") (class "Default")
      (node (ref "C100") (pin "1") (pintype "passive"))
      (node (ref "U11") (pin "17") (pinfunction "OUT3_17") (pintype "passive"))
      (node (ref "U8") (pin "6") (pinfunction "SENSOR_CAPP_6") (pintype "passive"))
    )
    (net (code "86") (name "/P38*") (class "Default")
      (node (ref "C101") (pin "2") (pintype "passive"))
      (node (ref "U11") (pin "18") (pinfunction "OUT2_18") (pintype "passive"))
      (node (ref "U8") (pin "7") (pinfunction "SENSOR_CAPN_7") (pintype "passive"))
    )
    (net (code "87") (name "/P39*") (class "Default")
      (node (ref "C101") (pin "1") (pintype "passive"))
      (node (ref "U11") (pin "20") (pinfunction "OUT1_20") (pintype "passive"))
      (node (ref "U8") (pin "8") (pinfunction "SENSOR_VN_8") (pintype "passive"))
    )
    (net (code "88") (name "/P60*") (class "Default")
      (node (ref "U8") (pin "23") (pinfunction "GPIO0_23") (pintype "passive"))
    )
    (net (code "89") (name "/P61*") (class "Default")
      (node (ref "U8") (pin "41") (pinfunction "U0TXD_41") (pintype "passive"))
    )
    (net (code "90") (name "/P62*") (class "Default")
      (node (ref "U8") (pin "22") (pinfunction "GPIO2_22") (pintype "passive"))
    )
    (net (code "91") (name "/P63*") (class "Default")
      (node (ref "U8") (pin "40") (pinfunction "U0RXD_40") (pintype "passive"))
    )
    (net (code "92") (name "/P64*") (class "Default")
      (node (ref "U8") (pin "24") (pinfunction "GPIO4_24") (pintype "passive"))
    )
    (net (code "93") (name "/P65*") (class "Default")
      (node (ref "U8") (pin "34") (pinfunction "GPIO5_34") (pintype "passive"))
    )
    (net (code "94") (name "/P66*") (class "Default")
      (node (ref "U10") (pin "6") (pinfunction "SCK_6") (pintype "input"))
      (node (ref "U8") (pin "31") (pinfunction "SD_CLK_31") (pintype "passive"))
    )
    (net (code "95") (name "/P67*") (class "Default")
      (node (ref "U10") (pin "2") (pinfunction "IO1_2") (pintype "bidirectional"))
      (node (ref "U8") (pin "32") (pinfunction "SD_DATA_0_32") (pintype "passive"))
    )
    (net (code "96") (name "/P68*") (class "Default")
      (node (ref "U10") (pin "5") (pinfunction "IO0_5") (pintype "bidirectional"))
      (node (ref "U8") (pin "33") (pinfunction "SD_DATA_1_33") (pintype "passive"))
    )
    (net (code "97") (name "/P69*") (class "Default")
      (node (ref "U10") (pin "3") (pinfunction "IO2/P#_3") (pintype "bidirectional"))
      (node (ref "U8") (pin "28") (pinfunction "SD_DATA_2_28") (pintype "passive"))
    )
    (net (code "98") (name "/P70*") (class "Default")
      (node (ref "U10") (pin "7") (pinfunction "IO3/H#_7") (pintype "bidirectional"))
      (node (ref "U8") (pin "29") (pinfunction "SD_DATA_3_29") (pintype "passive"))
    )
    (net (code "99") (name "/P71*") (class "Default")
      (node (ref "R52") (pin "2") (pintype "passive"))
      (node (ref "U10") (pin "1") (pinfunction "CE#_1") (pintype "input"))
      (node (ref "U8") (pin "30") (pinfunction "SD_CMD_30") (pintype "passive"))
    )
    (net (code "100") (name "/P72*") (class "Default")
      (node (ref "U8") (pin "18") (pinfunction "MTDI_18") (pintype "passive"))
    )
    (net (code "101") (name "/P73*") (class "Default")
      (node (ref "U8") (pin "20") (pinfunction "MTCK_20") (pintype "passive"))
    )
    (net (code "102") (name "/PPON") (class "Default")
      (node (ref "R33") (pin "2") (pintype "passive"))
      (node (ref "U8") (pin "9") (pinfunction "CHIP_PU_9") (pintype "passive"))
    )
    (net (code "103") (name "/PWRON") (class "Default")
      (node (ref "UM1") (pin "C6") (pinfunction "RUN1_C6") (pintype "passive"))
      (node (ref "UM1") (pin "F6") (pinfunction "RUN2_F6") (pintype "passive"))
    )
    (net (code "104") (name "/RAS#") (class "Default")
      (node (ref "R46") (pin "2") (pintype "passive"))
      (node (ref "U7") (pin "J3") (pinfunction "RAS#_J3") (pintype "passive"))
    )
    (net (code "105") (name "/RST#") (class "Default")
      (node (ref "R53") (pin "2") (pintype "passive"))
      (node (ref "U7") (pin "T2") (pinfunction "RESET#_T2") (pintype "passive"))
    )
    (net (code "106") (name "/UDM") (class "Default")
      (node (ref "R45") (pin "2") (pintype "passive"))
      (node (ref "U7") (pin "D3") (pinfunction "UDM_D3") (pintype "passive"))
    )
    (net (code "107") (name "/UD_N") (class "Default")
      (node (ref "U7") (pin "B7") (pinfunction "UDQS#_B7") (pintype "passive"))
    )
    (net (code "108") (name "/UD_P") (class "Default")
      (node (ref "U7") (pin "C7") (pinfunction "UDQS_C7") (pintype "passive"))
    )
    (net (code "109") (name "/USBID") (class "Default")
      (node (ref "U6") (pin "5") (pinfunction "ID_5") (pintype "passive"))
    )
    (net (code "110") (name "/USB_CLK") (class "Default")
      (node (ref "U6") (pin "14") (pinfunction "CLKOUT_14") (pintype "passive"))
    )
    (net (code "111") (name "/USB_D0") (class "Default")
      (node (ref "U6") (pin "24") (pinfunction "DATA0_24") (pintype "passive"))
    )
    (net (code "112") (name "/USB_D1") (class "Default")
      (node (ref "U6") (pin "23") (pinfunction "DATA1_23") (pintype "passive"))
    )
    (net (code "113") (name "/USB_D2") (class "Default")
      (node (ref "U6") (pin "22") (pinfunction "DATA2_22") (pintype "passive"))
    )
    (net (code "114") (name "/USB_D3") (class "Default")
      (node (ref "U6") (pin "21") (pinfunction "DATA3_21") (pintype "passive"))
    )
    (net (code "115") (name "/USB_D4") (class "Default")
      (node (ref "U6") (pin "20") (pinfunction "DATA4_20") (pintype "passive"))
    )
    (net (code "116") (name "/USB_D5") (class "Default")
      (node (ref "U6") (pin "19") (pinfunction "DATA5_19") (pintype "passive"))
    )
    (net (code "117") (name "/USB_D6") (class "Default")
      (node (ref "U6") (pin "18") (pinfunction "DATA6_18") (pintype "passive"))
    )
    (net (code "118") (name "/USB_D7") (class "Default")
      (node (ref "U6") (pin "17") (pinfunction "DATA7_17") (pintype "passive"))
    )
    (net (code "119") (name "/USB_DIR") (class "Default")
      (node (ref "U6") (pin "12") (pinfunction "DIR_12") (pintype "passive"))
    )
    (net (code "120") (name "/USB_NXT") (class "Default")
      (node (ref "U6") (pin "11") (pinfunction "NXT_11") (pintype "passive"))
    )
    (net (code "121") (name "/USB_STP") (class "Default")
      (node (ref "U6") (pin "13") (pinfunction "STP_13") (pintype "passive"))
    )
    (net (code "122") (name "/VBUS") (class "Default")
      (node (ref "C57") (pin "2") (pintype "passive"))
      (node (ref "R12") (pin "1") (pintype "passive"))
      (node (ref "R15") (pin "1") (pintype "passive"))
      (node (ref "U4") (pin "1") (pinfunction "VOUT_1") (pintype "passive"))
    )
    (net (code "123") (name "/VDD18") (class "Default")
      (node (ref "C62") (pin "2") (pintype "passive"))
      (node (ref "U6") (pin "15") (pinfunction "VDD1.8_15") (pintype "passive"))
      (node (ref "U6") (pin "26") (pinfunction "VDD1.8_26") (pintype "passive"))
    )
    (net (code "124") (name "/WE#") (class "Default")
      (node (ref "R48") (pin "2") (pintype "passive"))
      (node (ref "U7") (pin "L3") (pinfunction "WE#_L3") (pintype "passive"))
    )
    (net (code "125") (name "/eCLK") (class "Default")
      (node (ref "U9") (pin "M6") (pinfunction "CLK_M6") (pintype "passive"))
    )
    (net (code "126") (name "/eCMD") (class "Default")
      (node (ref "U9") (pin "M5") (pinfunction "CMD_M5") (pintype "passive"))
    )
    (net (code "127") (name "/eDAT0") (class "Default")
      (node (ref "U9") (pin "A3") (pinfunction "DAT0_A3") (pintype "passive"))
    )
    (net (code "128") (name "/eDAT1") (class "Default")
      (node (ref "U9") (pin "A4") (pinfunction "DAT1_A4") (pintype "passive"))
    )
    (net (code "129") (name "/eDAT2") (class "Default")
      (node (ref "U9") (pin "A5") (pinfunction "DAT2_A5") (pintype "passive"))
    )
    (net (code "130") (name "/eDAT3") (class "Default")
      (node (ref "U9") (pin "B2") (pinfunction "DAT3_B2") (pintype "passive"))
    )
    (net (code "131") (name "/eDAT4") (class "Default")
      (node (ref "U9") (pin "B3") (pinfunction "DAT4_B3") (pintype "passive"))
    )
    (net (code "132") (name "/eDAT5") (class "Default")
      (node (ref "U9") (pin "B4") (pinfunction "DAT5_B4") (pintype "passive"))
    )
    (net (code "133") (name "/eDAT6") (class "Default")
      (node (ref "U9") (pin "B5") (pinfunction "DAT6_B5") (pintype "passive"))
    )
    (net (code "134") (name "/eDAT7") (class "Default")
      (node (ref "U9") (pin "B6") (pinfunction "DAT7_B6") (pintype "passive"))
    )
    (net (code "135") (name "/eRST#") (class "Default")
      (node (ref "R30") (pin "1") (pintype "passive"))
      (node (ref "U9") (pin "K5") (pinfunction "RST_n_K5") (pintype "passive"))
    )
    (net (code "136") (name "GND") (class "Default")
      (node (ref "C102") (pin "2") (pintype "passive"))
      (node (ref "C103") (pin "1") (pintype "passive"))
      (node (ref "C104") (pin "2") (pintype "passive"))
      (node (ref "C105") (pin "1") (pintype "passive"))
      (node (ref "C106") (pin "2") (pintype "passive"))
      (node (ref "C107") (pin "1") (pintype "passive"))
      (node (ref "C108") (pin "2") (pintype "passive"))
      (node (ref "C109") (pin "1") (pintype "passive"))
      (node (ref "C111") (pin "2") (pintype "passive"))
      (node (ref "C112") (pin "1") (pintype "passive"))
      (node (ref "C52") (pin "1") (pintype "passive"))
      (node (ref "C53") (pin "2") (pintype "passive"))
      (node (ref "C54") (pin "2") (pintype "passive"))
      (node (ref "C55") (pin "2") (pintype "passive"))
      (node (ref "C56") (pin "2") (pintype "passive"))
      (node (ref "C57") (pin "1") (pintype "passive"))
      (node (ref "C58") (pin "2") (pintype "passive"))
      (node (ref "C59") (pin "1") (pintype "passive"))
      (node (ref "C60") (pin "2") (pintype "passive"))
      (node (ref "C61") (pin "2") (pintype "passive"))
      (node (ref "C62") (pin "1") (pintype "passive"))
      (node (ref "C63") (pin "1") (pintype "passive"))
      (node (ref "C64") (pin "2") (pintype "passive"))
      (node (ref "C65") (pin "2") (pintype "passive"))
      (node (ref "C66") (pin "2") (pintype "passive"))
      (node (ref "C67") (pin "2") (pintype "passive"))
      (node (ref "C68") (pin "2") (pintype "passive"))
      (node (ref "C69") (pin "2") (pintype "passive"))
      (node (ref "C70") (pin "2") (pintype "passive"))
      (node (ref "C71") (pin "2") (pintype "passive"))
      (node (ref "C72") (pin "2") (pintype "passive"))
      (node (ref "C73") (pin "2") (pintype "passive"))
      (node (ref "C74") (pin "1") (pintype "passive"))
      (node (ref "C75") (pin "2") (pintype "passive"))
      (node (ref "C76") (pin "1") (pintype "passive"))
      (node (ref "C77") (pin "2") (pintype "passive"))
      (node (ref "C78") (pin "2") (pintype "passive"))
      (node (ref "C79") (pin "1") (pintype "passive"))
      (node (ref "C80") (pin "1") (pintype "passive"))
      (node (ref "C81") (pin "2") (pintype "passive"))
      (node (ref "C82") (pin "1") (pintype "passive"))
      (node (ref "C83") (pin "2") (pintype "passive"))
      (node (ref "C84") (pin "2") (pintype "passive"))
      (node (ref "C86") (pin "2") (pintype "passive"))
      (node (ref "C88") (pin "2") (pintype "passive"))
      (node (ref "C89") (pin "2") (pintype "passive"))
      (node (ref "C90") (pin "2") (pintype "passive"))
      (node (ref "C91") (pin "2") (pintype "passive"))
      (node (ref "C92") (pin "1") (pintype "passive"))
      (node (ref "C94") (pin "2") (pintype "passive"))
      (node (ref "C95") (pin "1") (pintype "passive"))
      (node (ref "C96") (pin "1") (pintype "passive"))
      (node (ref "C97") (pin "1") (pintype "passive"))
      (node (ref "C98") (pin "2") (pintype "passive"))
      (node (ref "C99") (pin "2") (pintype "passive"))
      (node (ref "L5") (pin "1") (pintype "passive"))
      (node (ref "R11") (pin "1") (pintype "passive"))
      (node (ref "R14") (pin "2") (pintype "passive"))
      (node (ref "R16") (pin "2") (pintype "passive"))
      (node (ref "R17") (pin "2") (pintype "passive"))
      (node (ref "R20") (pin "2") (pintype "passive"))
      (node (ref "R21") (pin "2") (pintype "passive"))
      (node (ref "R22") (pin "1") (pintype "passive"))
      (node (ref "R33") (pin "1") (pintype "passive"))
      (node (ref "R50") (pin "1") (pintype "passive"))
      (node (ref "R55") (pin "1") (pintype "passive"))
      (node (ref "U10") (pin "4") (pinfunction "GND_4") (pintype "power_in"))
      (node (ref "U11") (pin "1") (pinfunction "INA_1") (pintype "passive"))
      (node (ref "U11") (pin "12") (pinfunction "PGND_12") (pintype "passive"))
      (node (ref "U11") (pin "19") (pinfunction "PGND_19") (pintype "passive"))
      (node (ref "U11") (pin "23") (pinfunction "SGND_23") (pintype "passive"))
      (node (ref "U11") (pin "25") (pinfunction "PAD_25") (pintype "passive"))
      (node (ref "U12") (pin "4") (pinfunction "GND_4") (pintype "passive"))
      (node (ref "U12") (pin "5") (pinfunction "PAD_5") (pintype "passive"))
      (node (ref "U4") (pin "4") (pinfunction "GND_4") (pintype "passive"))
      (node (ref "U4") (pin "5") (pinfunction "PAD_5") (pintype "passive"))
      (node (ref "U5") (pin "5") (pinfunction "GND_5") (pintype "passive"))
      (node (ref "U5") (pin "8") (pinfunction "AINM_8") (pintype "passive"))
      (node (ref "U6") (pin "1") (pinfunction "GND_1") (pintype "passive"))
      (node (ref "U6") (pin "2") (pinfunction "GND_2") (pintype "passive"))
      (node (ref "U6") (pin "33") (pinfunction "PAD_33") (pintype "passive"))
      (node (ref "U6") (pin "9") (pinfunction "RESET_9") (pintype "passive"))
      (node (ref "U7") (pin "A9") (pinfunction "Vss_A9") (pintype "passive"))
      (node (ref "U7") (pin "B1") (pinfunction "Vssq_B1") (pintype "passive"))
      (node (ref "U7") (pin "B3") (pinfunction "Vss_B3") (pintype "passive"))
      (node (ref "U7") (pin "B9") (pinfunction "Vssq_B9") (pintype "passive"))
      (node (ref "U7") (pin "D1") (pinfunction "Vssq_D1") (pintype "passive"))
      (node (ref "U7") (pin "D8") (pinfunction "Vssq_D8") (pintype "passive"))
      (node (ref "U7") (pin "E1") (pinfunction "Vss_E1") (pintype "passive"))
      (node (ref "U7") (pin "E2") (pinfunction "Vssq_E2") (pintype "passive"))
      (node (ref "U7") (pin "E8") (pinfunction "Vssq_E8") (pintype "passive"))
      (node (ref "U7") (pin "F9") (pinfunction "Vssq_F9") (pintype "passive"))
      (node (ref "U7") (pin "G1") (pinfunction "Vssq_G1") (pintype "passive"))
      (node (ref "U7") (pin "G8") (pinfunction "Vss_G8") (pintype "passive"))
      (node (ref "U7") (pin "G9") (pinfunction "Vssq_G9") (pintype "passive"))
      (node (ref "U7") (pin "J2") (pinfunction "Vss_J2") (pintype "passive"))
      (node (ref "U7") (pin "J8") (pinfunction "Vss_J8") (pintype "passive"))
      (node (ref "U7") (pin "M1") (pinfunction "Vss_M1") (pintype "passive"))
      (node (ref "U7") (pin "M9") (pinfunction "Vss_M9") (pintype "passive"))
      (node (ref "U7") (pin "P1") (pinfunction "Vss_P1") (pintype "passive"))
      (node (ref "U7") (pin "P9") (pinfunction "Vss_P9") (pintype "passive"))
      (node (ref "U7") (pin "T1") (pinfunction "Vss_T1") (pintype "passive"))
      (node (ref "U7") (pin "T9") (pinfunction "Vss_T9") (pintype "passive"))
      (node (ref "U8") (pin "49") (pinfunction "GND_49") (pintype "passive"))
      (node (ref "U9") (pin "C4") (pinfunction "Vssq_C4") (pintype "passive"))
      (node (ref "U9") (pin "E7") (pinfunction "Vss_E7") (pintype "passive"))
      (node (ref "U9") (pin "G5") (pinfunction "Vss_G5") (pintype "passive"))
      (node (ref "U9") (pin "H10") (pinfunction "Vss_H10") (pintype "passive"))
      (node (ref "U9") (pin "K8") (pinfunction "Vss_K8") (pintype "passive"))
      (node (ref "U9") (pin "N2") (pinfunction "Vssq_N2") (pintype "passive"))
      (node (ref "U9") (pin "N5") (pinfunction "Vssq_N5") (pintype "passive"))
      (node (ref "U9") (pin "P3") (pinfunction "Vssq_P3") (pintype "passive"))
      (node (ref "U9") (pin "P5") (pinfunction "Vssq_P5") (pintype "passive"))
      (node (ref "UM1") (pin "A4") (pinfunction "GND_A4") (pintype "passive"))
      (node (ref "UM1") (pin "A5") (pinfunction "GND_A5") (pintype "passive"))
      (node (ref "UM1") (pin "B1") (pinfunction "GND_B1") (pintype "passive"))
      (node (ref "UM1") (pin "B2") (pinfunction "GND_B2") (pintype "passive"))
      (node (ref "UM1") (pin "C5") (pinfunction "GND_C5") (pintype "passive"))
      (node (ref "UM1") (pin "D3") (pinfunction "GND_D3") (pintype "passive"))
      (node (ref "UM1") (pin "D4") (pinfunction "GND_D4") (pintype "passive"))
      (node (ref "UM1") (pin "D5") (pinfunction "GND_D5") (pintype "passive"))
      (node (ref "UM1") (pin "E1") (pinfunction "GND_E1") (pintype "passive"))
      (node (ref "UM1") (pin "E2") (pinfunction "GND_E2") (pintype "passive"))
      (node (ref "UM1") (pin "F5") (pinfunction "GND_F5") (pintype "passive"))
      (node (ref "UM1") (pin "F7") (pinfunction "SGND_F7") (pintype "passive"))
      (node (ref "UM1") (pin "G3") (pinfunction "GND_G3") (pintype "passive"))
      (node (ref "UM1") (pin "G4") (pinfunction "GND_G4") (pintype "passive"))
      (node (ref "UM1") (pin "G5") (pinfunction "GND_G5") (pintype "passive"))
      (node (ref "UM1") (pin "H1") (pinfunction "GND_H1") (pintype "passive"))
      (node (ref "UM1") (pin "H2") (pinfunction "GND_H2") (pintype "passive"))
      (node (ref "UM1") (pin "J5") (pinfunction "GND_J5") (pintype "passive"))
      (node (ref "UM1") (pin "K3") (pinfunction "GND_K3") (pintype "passive"))
      (node (ref "UM1") (pin "K4") (pinfunction "GND_K4") (pintype "passive"))
      (node (ref "UM1") (pin "L1") (pinfunction "GND_L1") (pintype "passive"))
      (node (ref "UM1") (pin "L2") (pinfunction "GND_L2") (pintype "passive"))
    )
    (net (code "137") (name "Net-(C110-Pad1)") (class "Default")
      (node (ref "C110") (pin "1") (pintype "passive"))
      (node (ref "R49") (pin "1") (pintype "passive"))
      (node (ref "R54") (pin "1") (pintype "passive"))
    )
    (net (code "138") (name "Net-(U4-EN)") (class "Default")
      (node (ref "U4") (pin "2") (pinfunction "EN_2") (pintype "passive"))
      (node (ref "U6") (pin "3") (pinfunction "CPEN_3") (pintype "passive"))
    )
    (net (code "139") (name "Net-(U5-AINP)") (class "Default")
      (node (ref "R13") (pin "1") (pintype "passive"))
      (node (ref "U5") (pin "7") (pinfunction "AINP_7") (pintype "passive"))
      (node (ref "UM1") (pin "F3") (pinfunction "TEMP_F3") (pintype "passive"))
    )
    (net (code "140") (name "Net-(U5-AVDD)") (class "Default")
      (node (ref "C56") (pin "1") (pintype "passive"))
      (node (ref "L3") (pin "2") (pintype "passive"))
      (node (ref "R13") (pin "2") (pintype "passive"))
      (node (ref "U5") (pin "6") (pinfunction "AVDD_6") (pintype "passive"))
    )
    (net (code "141") (name "Net-(U6-EXTVBUS)") (class "Default")
      (node (ref "R15") (pin "2") (pintype "passive"))
      (node (ref "U6") (pin "10") (pinfunction "EXTVBUS_10") (pintype "passive"))
    )
    (net (code "142") (name "Net-(U6-RBIAS)") (class "Default")
      (node (ref "R11") (pin "2") (pintype "passive"))
      (node (ref "U6") (pin "32") (pinfunction "RBIAS_32") (pintype "passive"))
    )
    (net (code "143") (name "Net-(U6-VBUS)") (class "Default")
      (node (ref "R12") (pin "2") (pintype "passive"))
      (node (ref "U6") (pin "4") (pinfunction "VBUS_4") (pintype "passive"))
    )
    (net (code "144") (name "Net-(U6-VDDA1.8)") (class "Default")
      (node (ref "C59") (pin "2") (pintype "passive"))
      (node (ref "U6") (pin "29") (pinfunction "VDDA1.8_29") (pintype "passive"))
    )
    (net (code "145") (name "Net-(U7-ZQ)") (class "Default")
      (node (ref "R20") (pin "1") (pintype "passive"))
      (node (ref "U7") (pin "L8") (pinfunction "ZQ_L8") (pintype "passive"))
    )
    (net (code "146") (name "Net-(U8-CAP1)") (class "Default")
      (node (ref "C79") (pin "2") (pintype "passive"))
      (node (ref "C85") (pin "1") (pintype "passive"))
      (node (ref "R18") (pin "2") (pintype "passive"))
      (node (ref "U8") (pin "48") (pinfunction "CAP1_48") (pintype "passive"))
    )
    (net (code "147") (name "Net-(U8-CAP2)") (class "Default")
      (node (ref "C85") (pin "2") (pintype "passive"))
      (node (ref "R18") (pin "1") (pintype "passive"))
      (node (ref "U8") (pin "47") (pinfunction "CAP2_47") (pintype "passive"))
    )
    (net (code "148") (name "Net-(U8-LNA_IN)") (class "Default")
      (node (ref "C87") (pin "2") (pintype "passive"))
      (node (ref "L5") (pin "2") (pintype "passive"))
      (node (ref "U8") (pin "2") (pinfunction "LNA_IN_2") (pintype "passive"))
    )
    (net (code "149") (name "Net-(U9-Vddim)") (class "Default")
      (node (ref "C107") (pin "2") (pintype "passive"))
      (node (ref "U9") (pin "C2") (pinfunction "Vddim_C2") (pintype "passive"))
    )
    (net (code "150") (name "Net-(U12-VOUT)") (class "Default")
      (node (ref "C111") (pin "1") (pintype "passive"))
      (node (ref "U11") (pin "10") (pinfunction "VM_10") (pintype "passive"))
      (node (ref "U11") (pin "21") (pinfunction "VM_21") (pintype "passive"))
      (node (ref "U12") (pin "1") (pinfunction "VOUT_1") (pintype "passive"))
    )
    (net (code "151") (name "Net-(UM1B-FB1)") (class "Default")
      (node (ref "R14") (pin "1") (pintype "passive"))
      (node (ref "UM1") (pin "A7") (pinfunction "FB1_A7") (pintype "passive"))
    )
    (net (code "152") (name "Net-(UM1B-INTVcc1)") (class "Default")
      (node (ref "UM1") (pin "B6") (pinfunction "MODE1_B6") (pintype "passive"))
      (node (ref "UM1") (pin "C4") (pinfunction "INTVcc1_C4") (pintype "passive"))
    )
    (net (code "153") (name "Net-(UM1B-TRACK{slash}SS1)") (class "Default")
      (node (ref "C58") (pin "1") (pintype "passive"))
      (node (ref "UM1") (pin "A6") (pinfunction "TRACK/SS1_A6") (pintype "passive"))
    )
    (net (code "154") (name "Net-(UM1C-FB2)") (class "Default")
      (node (ref "R16") (pin "1") (pintype "passive"))
      (node (ref "UM1") (pin "D7") (pinfunction "FB2_D7") (pintype "passive"))
    )
    (net (code "155") (name "Net-(UM1C-INTVcc2)") (class "Default")
      (node (ref "UM1") (pin "E6") (pinfunction "MODE2_E6") (pintype "passive"))
      (node (ref "UM1") (pin "F4") (pinfunction "INTVcc2_F4") (pintype "passive"))
    )
    (net (code "156") (name "Net-(UM1C-TRACK{slash}SS2)") (class "Default")
      (node (ref "C61") (pin "1") (pintype "passive"))
      (node (ref "UM1") (pin "D6") (pinfunction "TRACK/SS2_D6") (pintype "passive"))
    )
    (net (code "157") (name "Net-(UM1D-FB3)") (class "Default")
      (node (ref "R17") (pin "1") (pintype "passive"))
      (node (ref "UM1") (pin "G7") (pinfunction "FB3_G7") (pintype "passive"))
    )
    (net (code "158") (name "Net-(UM1D-INTVcc3)") (class "Default")
      (node (ref "UM1") (pin "H6") (pinfunction "MODE3_H6") (pintype "passive"))
      (node (ref "UM1") (pin "J4") (pinfunction "INTVcc3_J4") (pintype "passive"))
    )
    (net (code "159") (name "Net-(UM1D-TRACK{slash}SS3)") (class "Default")
      (node (ref "C73") (pin "1") (pintype "passive"))
      (node (ref "UM1") (pin "G6") (pinfunction "TRACK/SS3_G6") (pintype "passive"))
    )
    (net (code "160") (name "Net-(UM1E-FB4)") (class "Default")
      (node (ref "R21") (pin "1") (pintype "passive"))
      (node (ref "UM1") (pin "J7") (pinfunction "FB4_J7") (pintype "passive"))
    )
    (net (code "161") (name "Net-(UM1E-INTVcc4)") (class "Default")
      (node (ref "UM1") (pin "K5") (pinfunction "INTVcc4_K5") (pintype "passive"))
      (node (ref "UM1") (pin "L6") (pinfunction "MODE4_L6") (pintype "passive"))
    )
    (net (code "162") (name "Net-(UM1E-TRACK{slash}SS4)") (class "Default")
      (node (ref "C94") (pin "1") (pintype "passive"))
      (node (ref "UM1") (pin "K6") (pinfunction "TRACK/SS4_K6") (pintype "passive"))
    )
    (net (code "163") (name "unconnected-(U6-XO-Pad27)") (class "Default")
      (node (ref "U6") (pin "27") (pinfunction "XO_27") (pintype "passive+no_connect"))
    )
    (net (code "164") (name "unconnected-(U7-PadJ1)") (class "Default")
      (node (ref "U7") (pin "J1") (pintype "passive+no_connect"))
    )
    (net (code "165") (name "unconnected-(U7-PadJ9)") (class "Default")
      (node (ref "U7") (pin "J9") (pintype "passive+no_connect"))
    )
    (net (code "166") (name "unconnected-(U7-PadL1)") (class "Default")
      (node (ref "U7") (pin "L1") (pintype "passive+no_connect"))
    )
    (net (code "167") (name "unconnected-(U7-PadL9)") (class "Default")
      (node (ref "U7") (pin "L9") (pintype "passive+no_connect"))
    )
    (net (code "168") (name "unconnected-(U8-XTAL_N-Pad44)") (class "Default")
      (node (ref "U8") (pin "44") (pinfunction "XTAL_N_44") (pintype "passive+no_connect"))
    )
    (net (code "169") (name "unconnected-(U11-PI1-Pad24)") (class "Default")
      (node (ref "U11") (pin "24") (pinfunction "PI1_24") (pintype "passive+no_connect"))
    )
    (net (code "170") (name "unconnected-(UM1A-CLKIN-PadC7)") (class "Default")
      (node (ref "UM1") (pin "C7") (pinfunction "CLKIN_C7") (pintype "passive+no_connect"))
    )
    (net (code "171") (name "unconnected-(UM1A-CLKOUT-PadJ3)") (class "Default")
      (node (ref "UM1") (pin "J3") (pinfunction "CLKOUT_J3") (pintype "passive+no_connect"))
    )
    (net (code "172") (name "unconnected-(UM1B-COMP1-PadB7)") (class "Default")
      (node (ref "UM1") (pin "B7") (pinfunction "COMP1_B7") (pintype "passive+no_connect"))
    )
    (net (code "173") (name "unconnected-(UM1B-PGOOD1-PadC3)") (class "Default")
      (node (ref "UM1") (pin "C3") (pinfunction "PGOOD1_C3") (pintype "passive+no_connect"))
    )
    (net (code "174") (name "unconnected-(UM1C-COMP2-PadE7)") (class "Default")
      (node (ref "UM1") (pin "E7") (pinfunction "COMP2_E7") (pintype "passive+no_connect"))
    )
    (net (code "175") (name "unconnected-(UM1C-PGOOD2-PadC2)") (class "Default")
      (node (ref "UM1") (pin "C2") (pinfunction "PGOOD2_C2") (pintype "passive+no_connect"))
    )
    (net (code "176") (name "unconnected-(UM1D-COMP3-PadH7)") (class "Default")
      (node (ref "UM1") (pin "H7") (pinfunction "COMP3_H7") (pintype "passive+no_connect"))
    )
    (net (code "177") (name "unconnected-(UM1D-PGOOD3-PadF2)") (class "Default")
      (node (ref "UM1") (pin "F2") (pinfunction "PGOOD3_F2") (pintype "passive+no_connect"))
    )
    (net (code "178") (name "unconnected-(UM1E-COMP4-PadL7)") (class "Default")
      (node (ref "UM1") (pin "L7") (pinfunction "COMP4_L7") (pintype "passive+no_connect"))
    )
    (net (code "179") (name "unconnected-(UM1E-PGOOD4-PadJ2)") (class "Default")
      (node (ref "UM1") (pin "J2") (pinfunction "PGOOD4_J2") (pintype "passive+no_connect"))
    )
  )
)
